# CC3000MOD.net
KiCad netlist of a schematic drawn in Altium Designer
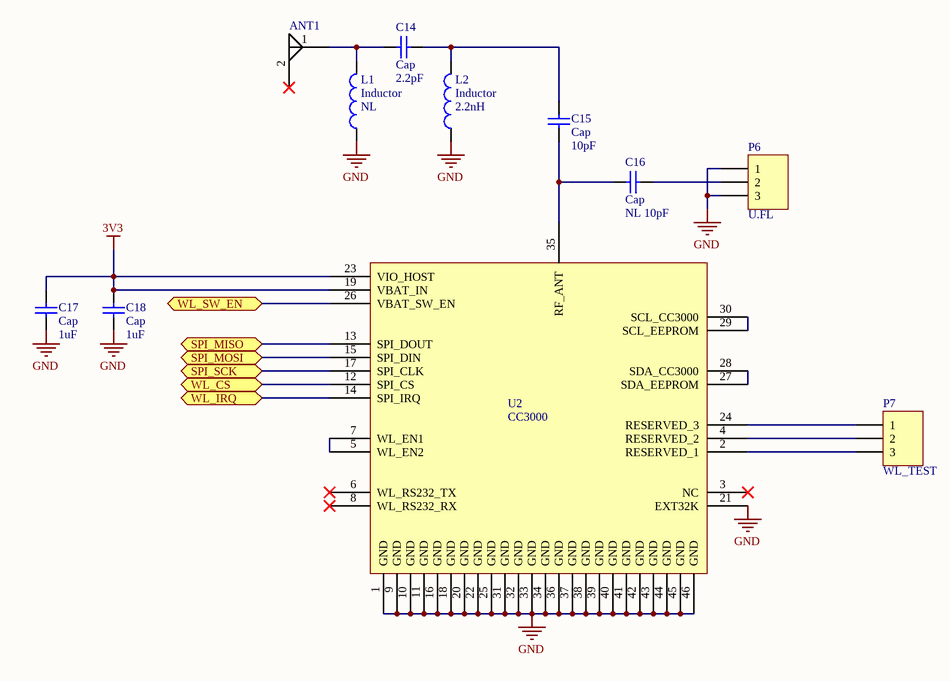
[diagram p0: CC3000MOD.SchDoc]

(export (version "E")
  (design (tool "Eeschema 10.0.6"))
  (components
    (comp (ref "ANT1")
      (value "ANT-SMT-2")
      (footprint "2500AT44M0400")
      (libsource (lib "BrewBit") (part "ANT-SMT-2"))
    )
    (comp (ref "C14")
      (value "Cap")
      (footprint "0402")
      (description "Capacitor")
      (fields (field (name "ALTIUM_VALUE") "2.2pF"))
      (libsource (lib "Miscellaneous Devices") (part "Cap"))
    )
    (comp (ref "C15")
      (value "Cap")
      (footprint "0402")
      (description "Capacitor")
      (fields (field (name "ALTIUM_VALUE") "10pF"))
      (libsource (lib "Miscellaneous Devices") (part "Cap"))
    )
    (comp (ref "C16")
      (value "Cap")
      (footprint "0402")
      (description "Capacitor")
      (fields (field (name "ALTIUM_VALUE") "NL 10pF"))
      (libsource (lib "Miscellaneous Devices") (part "Cap"))
    )
    (comp (ref "C17")
      (value "Cap")
      (footprint "0402")
      (description "Capacitor")
      (fields (field (name "ALTIUM_VALUE") "1uF"))
      (libsource (lib "Miscellaneous Devices") (part "Cap"))
    )
    (comp (ref "C18")
      (value "Cap")
      (footprint "0402")
      (description "Capacitor")
      (fields (field (name "ALTIUM_VALUE") "1uF"))
      (libsource (lib "Miscellaneous Devices") (part "Cap"))
    )
    (comp (ref "L1")
      (value "Inductor")
      (footprint "0402")
      (fields (field (name "ALTIUM_VALUE") "NL"))
      (libsource (lib "Miscellaneous Devices") (part "Inductor"))
    )
    (comp (ref "L2")
      (value "Inductor")
      (footprint "0402")
      (fields (field (name "ALTIUM_VALUE") "2.2nH"))
      (libsource (lib "Miscellaneous Devices") (part "Inductor"))
    )
    (comp (ref "P6")
      (value "U.FL")
      (footprint "U.FL-R-SMT-1")
      (description "Header, 3-Pin")
      (libsource (lib "Miscellaneous Connectors") (part "Header 3"))
    )
    (comp (ref "P7")
      (value "WL_TEST")
      (footprint "HDR1X3")
      (description "Header, 3-Pin")
      (libsource (lib "Miscellaneous Connectors") (part "Header 3"))
    )
    (comp (ref "U2")
      (value "CC3000")
      (footprint "CC3000")
      (description "CC3000 WLAN Module")
      (libsource (lib "BrewBit") (part "CC3000"))
    )
  )
  (nets
    (net (code "1") (name "/SPI_MISO") (class "Default")
      (node (ref "U2") (pin "13") (pinfunction "SPI_DOUT_13") (pintype "passive"))
    )
    (net (code "2") (name "/SPI_MOSI") (class "Default")
      (node (ref "U2") (pin "15") (pinfunction "SPI_DIN_15") (pintype "passive"))
    )
    (net (code "3") (name "/SPI_SCK") (class "Default")
      (node (ref "U2") (pin "17") (pinfunction "SPI_CLK_17") (pintype "passive"))
    )
    (net (code "4") (name "/WL_CS") (class "Default")
      (node (ref "U2") (pin "12") (pinfunction "SPI_CS_12") (pintype "passive"))
    )
    (net (code "5") (name "/WL_IRQ") (class "Default")
      (node (ref "U2") (pin "14") (pinfunction "SPI_IRQ_14") (pintype "passive"))
    )
    (net (code "6") (name "/WL_SW_EN") (class "Default")
      (node (ref "U2") (pin "26") (pinfunction "VBAT_SW_EN_26") (pintype "passive"))
    )
    (net (code "7") (name "3V3") (class "Default")
      (node (ref "C17") (pin "2") (pinfunction "2_2") (pintype "passive"))
      (node (ref "C18") (pin "2") (pinfunction "2_2") (pintype "passive"))
      (node (ref "U2") (pin "19") (pinfunction "VBAT_IN_19") (pintype "passive"))
      (node (ref "U2") (pin "23") (pinfunction "VIO_HOST_23") (pintype "passive"))
    )
    (net (code "8") (name "GND") (class "Default")
      (node (ref "C17") (pin "1") (pinfunction "1_1") (pintype "passive"))
      (node (ref "C18") (pin "1") (pinfunction "1_1") (pintype "passive"))
      (node (ref "L1") (pin "1") (pinfunction "1_1") (pintype "passive"))
      (node (ref "L2") (pin "1") (pinfunction "1_1") (pintype "passive"))
      (node (ref "P6") (pin "1") (pinfunction "1_1") (pintype "passive"))
      (node (ref "P6") (pin "3") (pinfunction "3_3") (pintype "passive"))
      (node (ref "U2") (pin "1") (pinfunction "GND_1") (pintype "passive"))
      (node (ref "U2") (pin "10") (pinfunction "GND_10") (pintype "passive"))
      (node (ref "U2") (pin "11") (pinfunction "GND_11") (pintype "passive"))
      (node (ref "U2") (pin "16") (pinfunction "GND_16") (pintype "passive"))
      (node (ref "U2") (pin "18") (pinfunction "GND_18") (pintype "passive"))
      (node (ref "U2") (pin "20") (pinfunction "GND_20") (pintype "passive"))
      (node (ref "U2") (pin "21") (pinfunction "EXT32K_21") (pintype "passive"))
      (node (ref "U2") (pin "22") (pinfunction "GND_22") (pintype "passive"))
      (node (ref "U2") (pin "25") (pinfunction "GND_25") (pintype "passive"))
      (node (ref "U2") (pin "31") (pinfunction "GND_31") (pintype "passive"))
      (node (ref "U2") (pin "32") (pinfunction "GND_32") (pintype "passive"))
      (node (ref "U2") (pin "33") (pinfunction "GND_33") (pintype "passive"))
      (node (ref "U2") (pin "34") (pinfunction "GND_34") (pintype "passive"))
      (node (ref "U2") (pin "36") (pinfunction "GND_36") (pintype "passive"))
      (node (ref "U2") (pin "37") (pinfunction "GND_37") (pintype "passive"))
      (node (ref "U2") (pin "38") (pinfunction "GND_38") (pintype "passive"))
      (node (ref "U2") (pin "39") (pinfunction "GND_39") (pintype "passive"))
      (node (ref "U2") (pin "40") (pinfunction "GND_40") (pintype "passive"))
      (node (ref "U2") (pin "41") (pinfunction "GND_41") (pintype "passive"))
      (node (ref "U2") (pin "42") (pinfunction "GND_42") (pintype "passive"))
      (node (ref "U2") (pin "43") (pinfunction "GND_43") (pintype "passive"))
      (node (ref "U2") (pin "44") (pinfunction "GND_44") (pintype "passive"))
      (node (ref "U2") (pin "45") (pinfunction "GND_45") (pintype "passive"))
      (node (ref "U2") (pin "46") (pinfunction "GND_46") (pintype "passive"))
      (node (ref "U2") (pin "9") (pinfunction "GND_9") (pintype "passive"))
    )
    (net (code "9") (name "Net-(ANT1-Pad1)") (class "Default")
      (node (ref "ANT1") (pin "1") (pintype "passive"))
      (node (ref "C14") (pin "1") (pinfunction "1_1") (pintype "passive"))
      (node (ref "L1") (pin "2") (pinfunction "2_2") (pintype "passive"))
    )
    (net (code "10") (name "Net-(C14-Pad2)") (class "Default")
      (node (ref "C14") (pin "2") (pinfunction "2_2") (pintype "passive"))
      (node (ref "C15") (pin "2") (pinfunction "2_2") (pintype "passive"))
      (node (ref "L2") (pin "2") (pinfunction "2_2") (pintype "passive"))
    )
    (net (code "11") (name "Net-(C16-Pad1)") (class "Default")
      (node (ref "C16") (pin "1") (pinfunction "1_1") (pintype "passive"))
      (node (ref "P6") (pin "2") (pinfunction "2_2") (pintype "passive"))
    )
    (net (code "12") (name "Net-(U2-RESERVED_1)") (class "Default")
      (node (ref "P7") (pin "3") (pinfunction "3_3") (pintype "passive"))
      (node (ref "U2") (pin "2") (pinfunction "RESERVED_1_2") (pintype "passive"))
    )
    (net (code "13") (name "Net-(U2-RESERVED_2)") (class "Default")
      (node (ref "P7") (pin "2") (pinfunction "2_2") (pintype "passive"))
      (node (ref "U2") (pin "4") (pinfunction "RESERVED_2_4") (pintype "passive"))
    )
    (net (code "14") (name "Net-(U2-RESERVED_3)") (class "Default")
      (node (ref "P7") (pin "1") (pinfunction "1_1") (pintype "passive"))
      (node (ref "U2") (pin "24") (pinfunction "RESERVED_3_24") (pintype "passive"))
    )
    (net (code "15") (name "Net-(U2-RF_ANT)") (class "Default")
      (node (ref "C15") (pin "1") (pinfunction "1_1") (pintype "passive"))
      (node (ref "C16") (pin "2") (pinfunction "2_2") (pintype "passive"))
      (node (ref "U2") (pin "35") (pinfunction "RF_ANT_35") (pintype "passive"))
    )
    (net (code "16") (name "Net-(U2-SCL_CC3000)") (class "Default")
      (node (ref "U2") (pin "29") (pinfunction "SCL_EEPROM_29") (pintype "passive"))
      (node (ref "U2") (pin "30") (pinfunction "SCL_CC3000_30") (pintype "passive"))
    )
    (net (code "17") (name "Net-(U2-SDA_CC3000)") (class "Default")
      (node (ref "U2") (pin "27") (pinfunction "SDA_EEPROM_27") (pintype "passive"))
      (node (ref "U2") (pin "28") (pinfunction "SDA_CC3000_28") (pintype "passive"))
    )
    (net (code "18") (name "Net-(U2-WL_EN1)") (class "Default")
      (node (ref "U2") (pin "5") (pinfunction "WL_EN2_5") (pintype "passive"))
      (node (ref "U2") (pin "7") (pinfunction "WL_EN1_7") (pintype "passive"))
    )
    (net (code "19") (name "unconnected-(ANT1-Pad2)") (class "Default")
      (node (ref "ANT1") (pin "2") (pintype "passive+no_connect"))
    )
    (net (code "20") (name "unconnected-(U2-NC-Pad3)") (class "Default")
      (node (ref "U2") (pin "3") (pinfunction "NC_3") (pintype "passive+no_connect"))
    )
    (net (code "21") (name "unconnected-(U2-WL_RS232_RX-Pad8)") (class "Default")
      (node (ref "U2") (pin "8") (pinfunction "WL_RS232_RX_8") (pintype "passive+no_connect"))
    )
    (net (code "22") (name "unconnected-(U2-WL_RS232_TX-Pad6)") (class "Default")
      (node (ref "U2") (pin "6") (pinfunction "WL_RS232_TX_6") (pintype "passive+no_connect"))
    )
  )
)
